# Sheet1.net
KiCad netlist of a schematic drawn in Altium Designer
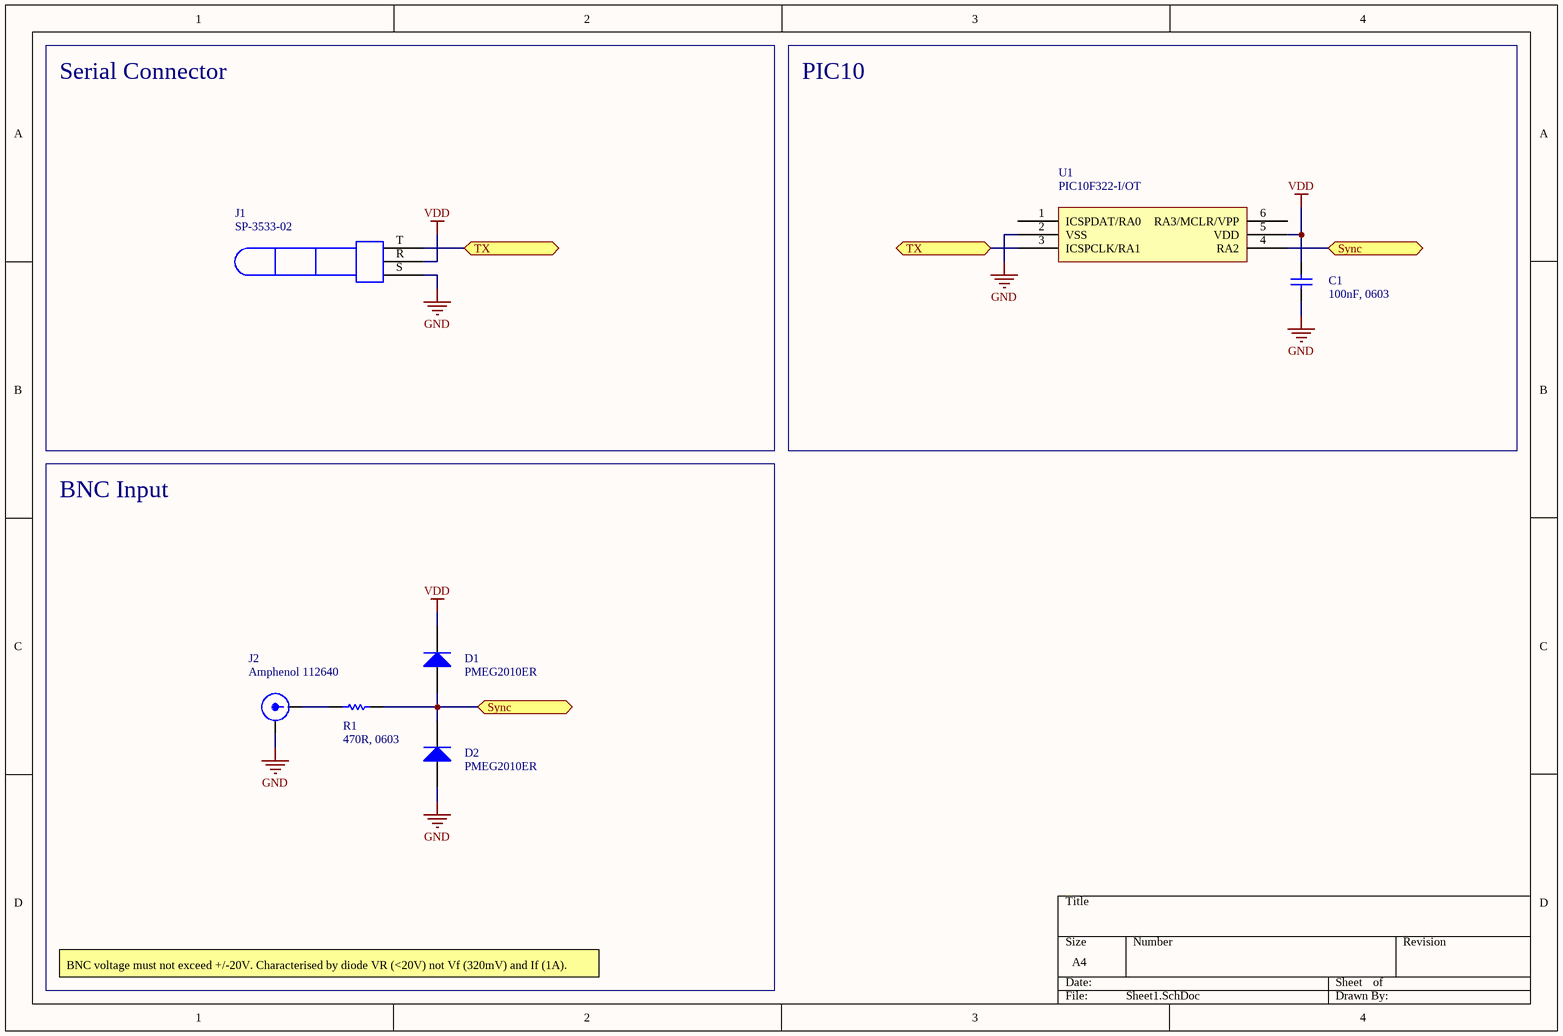
[diagram p0: Sheet1.SchDoc]

(export (version "E")
  (design (tool "Eeschema 10.0.6"))
  (components
    (comp (ref "C1")
      (value "100nF, 0603")
      (footprint "Capacitor 0603")
      (libsource (lib "x-io") (part "Capacitor"))
    )
    (comp (ref "D1") (value "PMEG2010ER") (footprint "SOD-123") (libsource (lib "x-io") (part "Diode")))
    (comp (ref "D2") (value "PMEG2010ER") (footprint "SOD-123") (libsource (lib "x-io") (part "Diode")))
    (comp (ref "J1")
      (value "SP-3533-02")
      (footprint "SP-3533-02")
      (libsource (lib "x-io") (part "SP-3533-02"))
    )
    (comp (ref "J2")
      (value "Amphenol 112640")
      (footprint "Amphenol 112640")
      (libsource (lib "x-io") (part "BNC"))
    )
    (comp (ref "R1")
      (value "470R, 0603")
      (footprint "Resistor 0603")
      (libsource (lib "x-io") (part "Resistor"))
    )
    (comp (ref "U1")
      (value "PIC10F322-I/OT")
      (footprint "SOT-23-6")
      (libsource (lib "x-io") (part "PIC10F322-I/OT"))
    )
  )
  (nets
    (net (code "1") (name "/Sync") (class "Default")
      (node (ref "D1") (pin "A") (pinfunction "A_A") (pintype "passive"))
      (node (ref "D2") (pin "K") (pinfunction "K_K") (pintype "passive"))
      (node (ref "R1") (pin "2") (pinfunction "2_2") (pintype "passive"))
      (node (ref "U1") (pin "4") (pinfunction "RA2_4") (pintype "passive"))
    )
    (net (code "2") (name "/TX") (class "Default")
      (node (ref "J1") (pin "T") (pinfunction "T_T") (pintype "passive"))
      (node (ref "U1") (pin "3") (pinfunction "ICSPCLK/RA1_3") (pintype "passive"))
    )
    (net (code "3") (name "GND") (class "Default")
      (node (ref "C1") (pin "1") (pinfunction "1_1") (pintype "passive"))
      (node (ref "D2") (pin "A") (pinfunction "A_A") (pintype "passive"))
      (node (ref "J1") (pin "S") (pinfunction "S_S") (pintype "passive"))
      (node (ref "J2") (pin "Shield") (pinfunction "Shield_Shield") (pintype "passive"))
      (node (ref "U1") (pin "2") (pinfunction "VSS_2") (pintype "passive"))
    )
    (net (code "4") (name "Net-(J2-PadSignal)") (class "Default")
      (node (ref "J2") (pin "Signal") (pinfunction "Signal_Signal") (pintype "passive"))
      (node (ref "R1") (pin "1") (pinfunction "1_1") (pintype "passive"))
    )
    (net (code "5") (name "VDD") (class "Default")
      (node (ref "C1") (pin "2") (pinfunction "2_2") (pintype "passive"))
      (node (ref "D1") (pin "K") (pinfunction "K_K") (pintype "passive"))
      (node (ref "J1") (pin "R") (pinfunction "R_R") (pintype "passive"))
      (node (ref "U1") (pin "5") (pinfunction "VDD_5") (pintype "passive"))
    )
    (net (code "6") (name "unconnected-(U1-ICSPDAT{slash}RA0-Pad1)") (class "Default")
      (node (ref "U1") (pin "1") (pinfunction "ICSPDAT/RA0_1") (pintype "passive"))
    )
    (net (code "7") (name "unconnected-(U1-RA3{slash}MCLR{slash}VPP-Pad6)") (class "Default")
      (node (ref "U1") (pin "6") (pinfunction "RA3/MCLR/VPP_6") (pintype "passive"))
    )
  )
)
